# EDm_v1_1.net
KiCad netlist of a schematic drawn in EAGLE
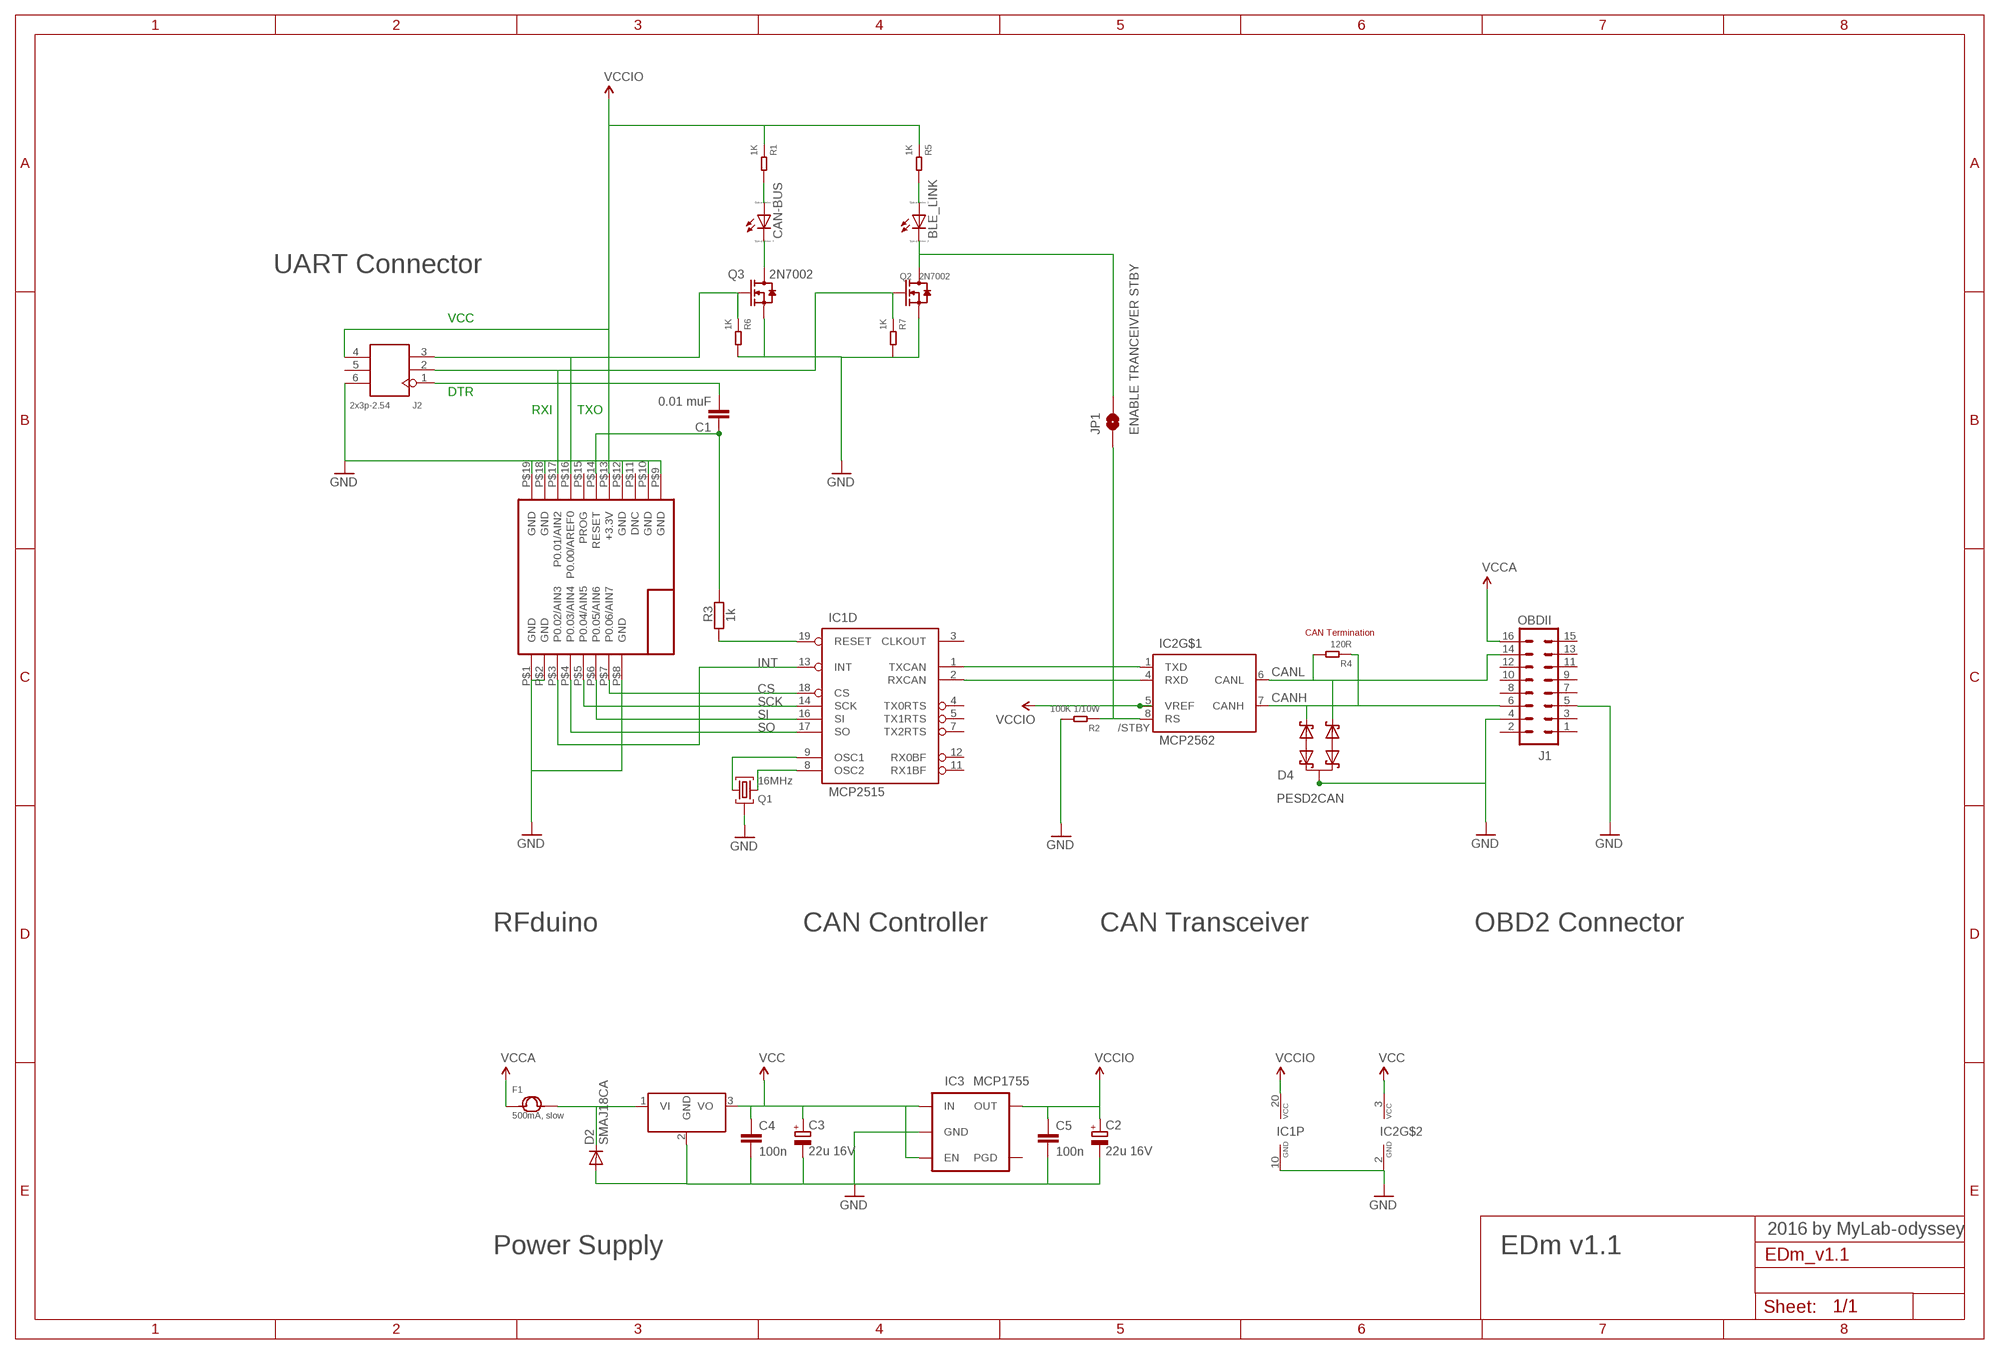
[diagram p0: schematic, sheet 1]

(export (version "E")
  (design (tool "Eeschema 10.0.6"))
  (components
    (comp (ref "78SR")
      (value "DCDC_OKI-78SR")
      (footprint "eagle-import:OKI-78SRH")
      (libsource (lib "eagle-import") (part "DCDC_OKI-78SR"))
    )
    (comp (ref "BLE_LINK")
      (value "LED_E")
      (footprint "eagle-import:LED_1206")
      (libsource (lib "eagle-import") (part "LED_E"))
    )
    (comp (ref "C1")
      (value "0.01 muF")
      (footprint "eagle-import:C0805")
      (libsource (lib "eagle-import") (part "C-EUC0805"))
    )
    (comp (ref "C2")
      (value "22u 16V")
      (footprint "eagle-import:SMC_A")
      (libsource (lib "eagle-import") (part "CPOL-EUSMCA"))
    )
    (comp (ref "C3")
      (value "22u 16V")
      (footprint "eagle-import:SMC_A")
      (libsource (lib "eagle-import") (part "CPOL-EUSMCA"))
    )
    (comp (ref "C4")
      (value "100n")
      (footprint "eagle-import:0805")
      (libsource (lib "eagle-import") (part "CAP0805"))
    )
    (comp (ref "C5")
      (value "100n")
      (footprint "eagle-import:0805")
      (libsource (lib "eagle-import") (part "CAP0805"))
    )
    (comp (ref "CAN-BUS")
      (value "LED_E")
      (footprint "eagle-import:LED_1206")
      (libsource (lib "eagle-import") (part "LED_E"))
    )
    (comp (ref "D2")
      (value "SMAJ18CA")
      (footprint "eagle-import:SMA-DIODE")
      (libsource (lib "eagle-import") (part "DIODESMA"))
    )
    (comp (ref "D4")
      (value "PESD2CAN")
      (footprint "eagle-import:SOT23")
      (libsource (lib "eagle-import") (part "PESD2CAN"))
    )
    (comp (ref "F1")
      (value "500mA, slow")
      (footprint "eagle-import:F3366")
      (libsource (lib "eagle-import") (part "FUSE500MA"))
    )
    (comp (ref "IC1")
      (value "MCP2515")
      (footprint "eagle-import:TSSOP20")
      (libsource (lib "eagle-import") (part "MCP2515ST"))
    )
    (comp (ref "IC2")
      (value "MCP2562")
      (footprint "eagle-import:SO08")
      (libsource (lib "eagle-import") (part "MCP2551SO8"))
    )
    (comp (ref "IC3")
      (value "MCP1755")
      (footprint "eagle-import:SOT23-5")
      (libsource (lib "eagle-import") (part "MCP1755"))
    )
    (comp (ref "J1")
      (value "OBDII")
      (footprint "eagle-import:OBDII-COMTECH")
      (fields (field (name "PARTNO") "OBD-II"))
      (libsource (lib "eagle-import") (part "M08X2-OBDII-COMTECH"))
    )
    (comp (ref "J2")
      (value "2x3p-2.54")
      (footprint "eagle-import:H2X3-2.54")
      (fields (field (name "MPN") "F185-1203A1BSYA1"))
      (libsource (lib "eagle-import") (part "DIP-BLACK-FEMALE-HEADER-VERT(2X3P-2.54)"))
    )
    (comp (ref "JP1")
      (value "ENABLE TRANCEIVER STBY")
      (footprint "eagle-import:PAD-JUMPER-2-NO_YES_SILK")
      (libsource (lib "eagle-import") (part "JUMPER-PAD-2-NOYES_SILK"))
    )
    (comp (ref "Q1")
      (value "16MHz")
      (footprint "eagle-import:SMD_OSC_35X15")
      (libsource (lib "eagle-import") (part "SMD_OSC2"))
    )
    (comp (ref "Q2")
      (value "2N7002")
      (footprint "eagle-import:SOT-23")
      (fields (field (name "MPN") "2N7002,215"))
      (libsource (lib "eagle-import") (part "SMD-MOSFET-N-CH-60V-300MA-LOGIC-LEVEL-FET-2N7002(SOT-23)"))
    )
    (comp (ref "Q3")
      (value "2N7002")
      (footprint "eagle-import:SOT-23")
      (fields (field (name "MPN") "2N7002,215"))
      (libsource (lib "eagle-import") (part "SMD-MOSFET-N-CH-60V-300MA-LOGIC-LEVEL-FET-2N7002(SOT-23)"))
    )
    (comp (ref "R1")
      (value "1K")
      (footprint "eagle-import:R0603")
      (fields (field (name "MPN") "RC0603FR-071KL"))
      (libsource (lib "eagle-import") (part "SMD-RES-1K-1%-1/10W(0603)"))
    )
    (comp (ref "R2")
      (value "100K 1/10W")
      (footprint "eagle-import:R0603")
      (fields (field (name "MPN") "RC0603JR-07100KL"))
      (libsource (lib "eagle-import") (part "SMD-RES-100K-5%-1/10W(0603)"))
    )
    (comp (ref "R3")
      (value "1k")
      (footprint "eagle-import:R0603")
      (libsource (lib "eagle-import") (part "R-EU_R0603"))
    )
    (comp (ref "R4")
      (value "120R")
      (footprint "eagle-import:R0603")
      (fields (field (name "MPN") "RC0603FR-07120RL"))
      (libsource (lib "eagle-import") (part "SMD-RES-120R-1%-1/10W(0603)"))
    )
    (comp (ref "R5")
      (value "1K")
      (footprint "eagle-import:R0603")
      (fields (field (name "MPN") "RC0603FR-071KL"))
      (libsource (lib "eagle-import") (part "SMD-RES-1K-1%-1/10W(0603)"))
    )
    (comp (ref "R6")
      (value "1K")
      (footprint "eagle-import:R0603")
      (fields (field (name "MPN") "RC0603FR-071KL"))
      (libsource (lib "eagle-import") (part "SMD-RES-1K-1%-1/10W(0603)"))
    )
    (comp (ref "R7")
      (value "1K")
      (footprint "eagle-import:R0603")
      (fields (field (name "MPN") "RC0603FR-071KL"))
      (libsource (lib "eagle-import") (part "SMD-RES-1K-1%-1/10W(0603)"))
    )
    (comp (ref "RFDUINO")
      (value "RFD22301")
      (footprint "eagle-import:RFD21733")
      (libsource (lib "eagle-import") (part "RFD22301"))
    )
  )
  (nets
    (net (code "1") (name "/CANH") (class "Default")
      (node (ref "D4") (pin "1") (pinfunction "1_1") (pintype "passive"))
      (node (ref "IC2") (pin "7") (pinfunction "CANH_7") (pintype "bidirectional"))
      (node (ref "J1") (pin "6") (pinfunction "6_6") (pintype "passive"))
      (node (ref "R4") (pin "1") (pinfunction "1_1") (pintype "passive"))
    )
    (net (code "2") (name "/CANL") (class "Default")
      (node (ref "D4") (pin "2") (pinfunction "2_2") (pintype "passive"))
      (node (ref "IC2") (pin "6") (pinfunction "CANL_6") (pintype "bidirectional"))
      (node (ref "J1") (pin "14") (pinfunction "14_14") (pintype "passive"))
      (node (ref "R4") (pin "2") (pinfunction "2_2") (pintype "passive"))
    )
    (net (code "3") (name "/CS") (class "Default")
      (node (ref "IC1") (pin "18") (pinfunction "CS_18") (pintype "input"))
      (node (ref "RFDUINO") (pin "P$7") (pinfunction "P0.06/AIN7_P$7") (pintype "bidirectional"))
    )
    (net (code "4") (name "/INT") (class "Default")
      (node (ref "IC1") (pin "13") (pinfunction "INT_13") (pintype "output"))
      (node (ref "RFDUINO") (pin "P$3") (pinfunction "P0.02/AIN3_P$3") (pintype "bidirectional"))
    )
    (net (code "5") (name "/SCK") (class "Default")
      (node (ref "IC1") (pin "14") (pinfunction "SCK_14") (pintype "input"))
      (node (ref "RFDUINO") (pin "P$5") (pinfunction "P0.04/AIN5_P$5") (pintype "bidirectional"))
    )
    (net (code "6") (name "/SI") (class "Default")
      (node (ref "IC1") (pin "16") (pinfunction "SI_16") (pintype "input"))
      (node (ref "RFDUINO") (pin "P$6") (pinfunction "P0.05/AIN6_P$6") (pintype "bidirectional"))
    )
    (net (code "7") (name "/SO") (class "Default")
      (node (ref "IC1") (pin "17") (pinfunction "SO_17") (pintype "output"))
      (node (ref "RFDUINO") (pin "P$4") (pinfunction "P0.03/AIN4_P$4") (pintype "bidirectional"))
    )
    (net (code "8") (name "GND") (class "Default")
      (node (ref "78SR") (pin "2") (pinfunction "GND_2") (pintype "bidirectional"))
      (node (ref "C2") (pin "-") (pinfunction "-_-") (pintype "passive"))
      (node (ref "C3") (pin "-") (pinfunction "-_-") (pintype "passive"))
      (node (ref "C4") (pin "2") (pinfunction "2_2") (pintype "passive"))
      (node (ref "C5") (pin "2") (pinfunction "2_2") (pintype "passive"))
      (node (ref "D2") (pin "A") (pinfunction "A_A") (pintype "passive"))
      (node (ref "D4") (pin "3") (pinfunction "3_3") (pintype "passive"))
      (node (ref "IC1") (pin "10") (pinfunction "GND_10") (pintype "power_in"))
      (node (ref "IC2") (pin "2") (pinfunction "GND_2") (pintype "power_in"))
      (node (ref "IC3") (pin "2") (pinfunction "GND_2") (pintype "input"))
      (node (ref "J1") (pin "4") (pinfunction "4_4") (pintype "passive"))
      (node (ref "J1") (pin "5") (pinfunction "5_5") (pintype "passive"))
      (node (ref "J2") (pin "6") (pinfunction "6_6") (pintype "bidirectional"))
      (node (ref "Q1") (pin "GND") (pinfunction "GND_GND") (pintype "passive"))
      (node (ref "Q2") (pin "2") (pinfunction "S_2") (pintype "passive"))
      (node (ref "Q3") (pin "2") (pinfunction "S_2") (pintype "passive"))
      (node (ref "R2") (pin "2") (pinfunction "2_2") (pintype "passive"))
      (node (ref "R6") (pin "2") (pinfunction "2_2") (pintype "passive"))
      (node (ref "R7") (pin "2") (pinfunction "2_2") (pintype "passive"))
      (node (ref "RFDUINO") (pin "P$1") (pinfunction "GND_P$1") (pintype "bidirectional"))
      (node (ref "RFDUINO") (pin "P$10") (pinfunction "GND_P$10") (pintype "bidirectional"))
      (node (ref "RFDUINO") (pin "P$12") (pinfunction "GND_P$12") (pintype "bidirectional"))
      (node (ref "RFDUINO") (pin "P$18") (pinfunction "GND_P$18") (pintype "bidirectional"))
      (node (ref "RFDUINO") (pin "P$19") (pinfunction "GND_P$19") (pintype "bidirectional"))
      (node (ref "RFDUINO") (pin "P$2") (pinfunction "GND_P$2") (pintype "bidirectional"))
      (node (ref "RFDUINO") (pin "P$8") (pinfunction "GND_P$8") (pintype "bidirectional"))
      (node (ref "RFDUINO") (pin "P$9") (pinfunction "GND_P$9") (pintype "bidirectional"))
    )
    (net (code "9") (name "Net-(78SR-VI)") (class "Default")
      (node (ref "78SR") (pin "1") (pinfunction "VI_1") (pintype "bidirectional"))
      (node (ref "D2") (pin "C") (pinfunction "C_C") (pintype "passive"))
      (node (ref "F1") (pin "2") (pinfunction "2_2") (pintype "bidirectional"))
    )
    (net (code "10") (name "Net-(BLE_LINK-PadA)") (class "Default")
      (node (ref "BLE_LINK") (pin "A") (pinfunction "A_A") (pintype "passive"))
      (node (ref "R5") (pin "2") (pinfunction "2_2") (pintype "passive"))
    )
    (net (code "11") (name "Net-(C1-Pad2)") (class "Default")
      (node (ref "C1") (pin "2") (pinfunction "2_2") (pintype "passive"))
      (node (ref "J2") (pin "1") (pinfunction "1_1") (pintype "bidirectional"))
    )
    (net (code "12") (name "Net-(CAN-BUS-PadA)") (class "Default")
      (node (ref "CAN-BUS") (pin "A") (pinfunction "A_A") (pintype "passive"))
      (node (ref "R1") (pin "2") (pinfunction "2_2") (pintype "passive"))
    )
    (net (code "13") (name "Net-(IC1A-OSC1)") (class "Default")
      (node (ref "IC1") (pin "9") (pinfunction "OSC1_9") (pintype "input"))
      (node (ref "Q1") (pin "1") (pinfunction "1_1") (pintype "passive"))
    )
    (net (code "14") (name "Net-(IC1A-OSC2)") (class "Default")
      (node (ref "IC1") (pin "8") (pinfunction "OSC2_8") (pintype "input"))
      (node (ref "Q1") (pin "2") (pinfunction "2_2") (pintype "passive"))
    )
    (net (code "15") (name "Net-(IC1A-RESET)") (class "Default")
      (node (ref "IC1") (pin "19") (pinfunction "RESET_19") (pintype "input"))
      (node (ref "R3") (pin "2") (pinfunction "2_2") (pintype "passive"))
    )
    (net (code "16") (name "Net-(IC1A-RXCAN)") (class "Default")
      (node (ref "IC1") (pin "2") (pinfunction "RXCAN_2") (pintype "input"))
      (node (ref "IC2") (pin "4") (pinfunction "RXD_4") (pintype "bidirectional"))
    )
    (net (code "17") (name "Net-(IC1A-TXCAN)") (class "Default")
      (node (ref "IC1") (pin "1") (pinfunction "TXCAN_1") (pintype "output"))
      (node (ref "IC2") (pin "1") (pinfunction "TXD_1") (pintype "bidirectional"))
    )
    (net (code "18") (name "Net-(IC2A-RS)") (class "Default")
      (node (ref "IC2") (pin "8") (pinfunction "RS_8") (pintype "bidirectional"))
      (node (ref "JP1") (pin "1") (pinfunction "1_1") (pintype "passive"))
      (node (ref "R2") (pin "1") (pinfunction "1_1") (pintype "passive"))
    )
    (net (code "19") (name "Net-(Q2-D)") (class "Default")
      (node (ref "BLE_LINK") (pin "C") (pinfunction "C_C") (pintype "passive"))
      (node (ref "JP1") (pin "2") (pinfunction "2_2") (pintype "passive"))
      (node (ref "Q2") (pin "3") (pinfunction "D_3") (pintype "passive"))
    )
    (net (code "20") (name "Net-(Q2-G)") (class "Default")
      (node (ref "J2") (pin "2") (pinfunction "2_2") (pintype "bidirectional"))
      (node (ref "Q2") (pin "1") (pinfunction "G_1") (pintype "passive"))
      (node (ref "R7") (pin "1") (pinfunction "1_1") (pintype "passive"))
      (node (ref "RFDUINO") (pin "P$17") (pinfunction "P0.01/AIN2_P$17") (pintype "bidirectional"))
    )
    (net (code "21") (name "Net-(Q3-D)") (class "Default")
      (node (ref "CAN-BUS") (pin "C") (pinfunction "C_C") (pintype "passive"))
      (node (ref "Q3") (pin "3") (pinfunction "D_3") (pintype "passive"))
    )
    (net (code "22") (name "Net-(Q3-G)") (class "Default")
      (node (ref "J2") (pin "3") (pinfunction "3_3") (pintype "bidirectional"))
      (node (ref "Q3") (pin "1") (pinfunction "G_1") (pintype "passive"))
      (node (ref "R6") (pin "1") (pinfunction "1_1") (pintype "passive"))
      (node (ref "RFDUINO") (pin "P$16") (pinfunction "P0.00/AREF0_P$16") (pintype "bidirectional"))
    )
    (net (code "23") (name "Net-(RFDUINO-RESET)") (class "Default")
      (node (ref "C1") (pin "1") (pinfunction "1_1") (pintype "passive"))
      (node (ref "R3") (pin "1") (pinfunction "1_1") (pintype "passive"))
      (node (ref "RFDUINO") (pin "P$14") (pinfunction "RESET_P$14") (pintype "bidirectional"))
    )
    (net (code "24") (name "VCC") (class "Default")
      (node (ref "78SR") (pin "3") (pinfunction "VO_3") (pintype "bidirectional"))
      (node (ref "C3") (pin "+") (pinfunction "+_+") (pintype "passive"))
      (node (ref "C4") (pin "1") (pinfunction "1_1") (pintype "passive"))
      (node (ref "IC2") (pin "3") (pinfunction "VCC_3") (pintype "power_in"))
      (node (ref "IC3") (pin "1") (pinfunction "IN_1") (pintype "input"))
      (node (ref "IC3") (pin "3") (pinfunction "EN_3") (pintype "input"))
    )
    (net (code "25") (name "VCCA") (class "Default")
      (node (ref "F1") (pin "1") (pinfunction "1_1") (pintype "bidirectional"))
      (node (ref "J1") (pin "16") (pinfunction "16_16") (pintype "passive"))
    )
    (net (code "26") (name "VCCIO") (class "Default")
      (node (ref "C2") (pin "+") (pinfunction "+_+") (pintype "passive"))
      (node (ref "C5") (pin "1") (pinfunction "1_1") (pintype "passive"))
      (node (ref "IC1") (pin "20") (pinfunction "VCC_20") (pintype "power_in"))
      (node (ref "IC2") (pin "5") (pinfunction "VREF_5") (pintype "bidirectional"))
      (node (ref "IC3") (pin "5") (pinfunction "OUT_5") (pintype "passive"))
      (node (ref "J2") (pin "4") (pinfunction "4_4") (pintype "bidirectional"))
      (node (ref "R1") (pin "1") (pinfunction "1_1") (pintype "passive"))
      (node (ref "R5") (pin "1") (pinfunction "1_1") (pintype "passive"))
      (node (ref "RFDUINO") (pin "P$13") (pinfunction "+3.3V_P$13") (pintype "bidirectional"))
    )
    (net (code "27") (name "unconnected-(IC1A-CLKOUT-Pad3)") (class "Default")
      (node (ref "IC1") (pin "3") (pinfunction "CLKOUT_3") (pintype "output"))
    )
    (net (code "28") (name "unconnected-(IC1A-RX0BF-Pad12)") (class "Default")
      (node (ref "IC1") (pin "12") (pinfunction "RX0BF_12") (pintype "output"))
    )
    (net (code "29") (name "unconnected-(IC1A-RX1BF-Pad11)") (class "Default")
      (node (ref "IC1") (pin "11") (pinfunction "RX1BF_11") (pintype "output"))
    )
    (net (code "30") (name "unconnected-(IC1A-TX0RTS-Pad4)") (class "Default")
      (node (ref "IC1") (pin "4") (pinfunction "TX0RTS_4") (pintype "input"))
    )
    (net (code "31") (name "unconnected-(IC1A-TX1RTS-Pad5)") (class "Default")
      (node (ref "IC1") (pin "5") (pinfunction "TX1RTS_5") (pintype "input"))
    )
    (net (code "32") (name "unconnected-(IC1A-TX2RTS-Pad7)") (class "Default")
      (node (ref "IC1") (pin "7") (pinfunction "TX2RTS_7") (pintype "input"))
    )
    (net (code "33") (name "unconnected-(IC3-PGD-Pad4)") (class "Default")
      (node (ref "IC3") (pin "4") (pinfunction "PGD_4") (pintype "input"))
    )
    (net (code "34") (name "unconnected-(J1-Pad1)") (class "Default")
      (node (ref "J1") (pin "1") (pinfunction "1_1") (pintype "passive"))
    )
    (net (code "35") (name "unconnected-(J1-Pad2)") (class "Default")
      (node (ref "J1") (pin "2") (pinfunction "2_2") (pintype "passive"))
    )
    (net (code "36") (name "unconnected-(J1-Pad3)") (class "Default")
      (node (ref "J1") (pin "3") (pinfunction "3_3") (pintype "passive"))
    )
    (net (code "37") (name "unconnected-(J1-Pad7)") (class "Default")
      (node (ref "J1") (pin "7") (pinfunction "7_7") (pintype "passive"))
    )
    (net (code "38") (name "unconnected-(J1-Pad8)") (class "Default")
      (node (ref "J1") (pin "8") (pinfunction "8_8") (pintype "passive"))
    )
    (net (code "39") (name "unconnected-(J1-Pad9)") (class "Default")
      (node (ref "J1") (pin "9") (pinfunction "9_9") (pintype "passive"))
    )
    (net (code "40") (name "unconnected-(J1-Pad10)") (class "Default")
      (node (ref "J1") (pin "10") (pinfunction "10_10") (pintype "passive"))
    )
    (net (code "41") (name "unconnected-(J1-Pad11)") (class "Default")
      (node (ref "J1") (pin "11") (pinfunction "11_11") (pintype "passive"))
    )
    (net (code "42") (name "unconnected-(J1-Pad12)") (class "Default")
      (node (ref "J1") (pin "12") (pinfunction "12_12") (pintype "passive"))
    )
    (net (code "43") (name "unconnected-(J1-Pad13)") (class "Default")
      (node (ref "J1") (pin "13") (pinfunction "13_13") (pintype "passive"))
    )
    (net (code "44") (name "unconnected-(J1-Pad15)") (class "Default")
      (node (ref "J1") (pin "15") (pinfunction "15_15") (pintype "passive"))
    )
    (net (code "45") (name "unconnected-(J2-Pad5)") (class "Default")
      (node (ref "J2") (pin "5") (pinfunction "5_5") (pintype "bidirectional"))
    )
    (net (code "46") (name "unconnected-(RFDUINO-DNC-PadP$11)") (class "Default")
      (node (ref "RFDUINO") (pin "P$11") (pinfunction "DNC_P$11") (pintype "bidirectional"))
    )
    (net (code "47") (name "unconnected-(RFDUINO-PROG-PadP$15)") (class "Default")
      (node (ref "RFDUINO") (pin "P$15") (pinfunction "PROG_P$15") (pintype "bidirectional"))
    )
  )
)
